# Charging.net
KiCad netlist of a schematic drawn in Altium Designer
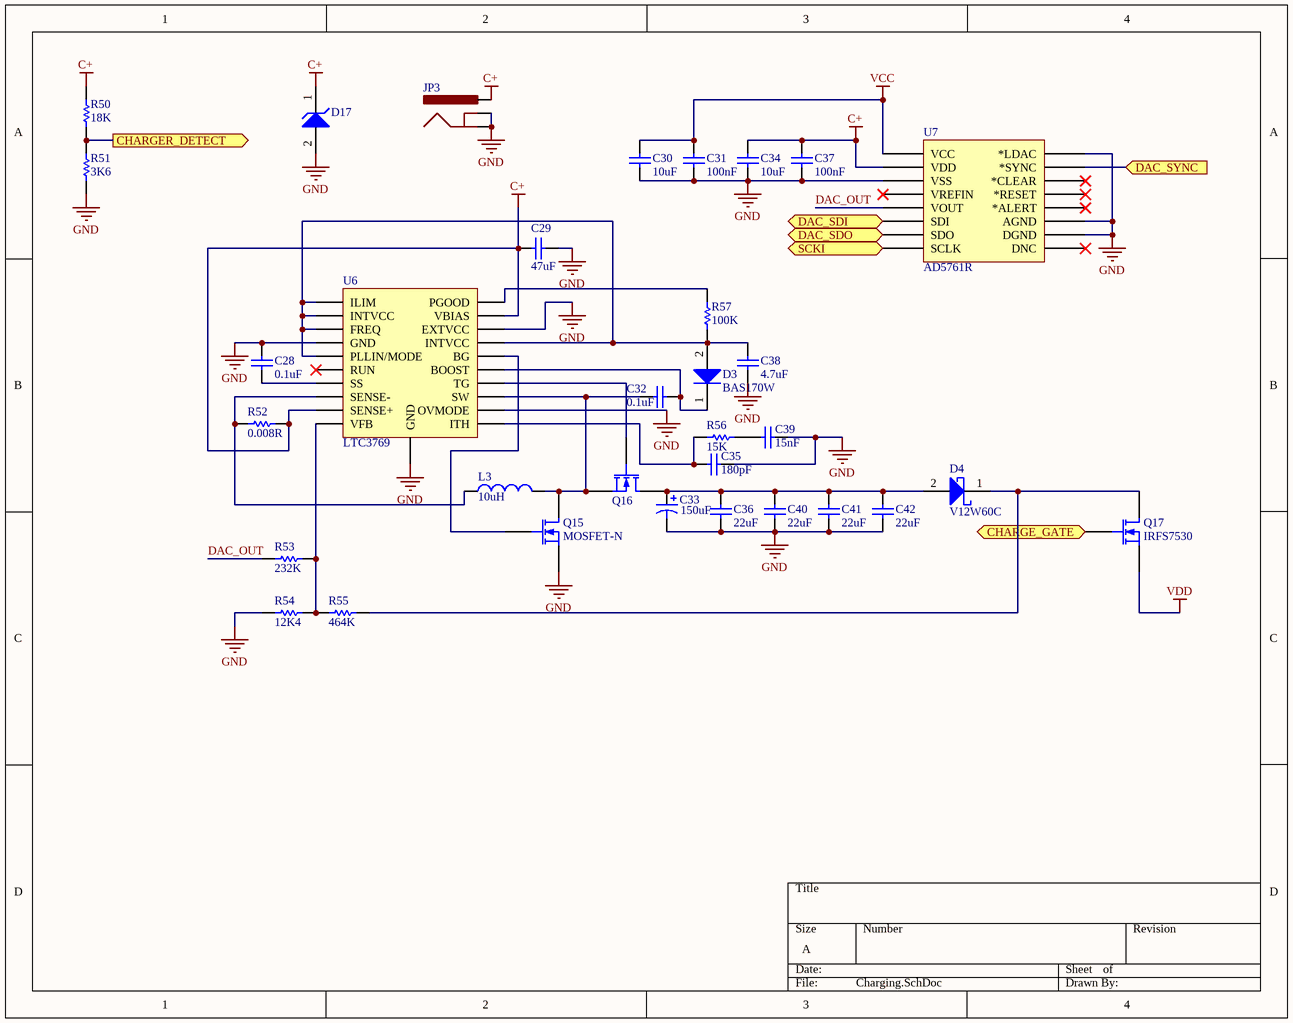
[diagram p0: Charging.SchDoc]

(export (version "E")
  (design (tool "Eeschema 10.0.6"))
  (components
    (comp (ref "C28")
      (value "0.1uF")
      (footprint "CAPC0603(1608)100_M")
      (description "CAP 100nF 6.3V Â±5% 0603 (1608 Metric) Thickness 1mm SMD")
      (fields (field (name "TOLERANCE") "Â±5%"))
      (libsource (lib "Altium Content Vault") (part "CAP"))
    )
    (comp (ref "C29")
      (value "47uF")
      (footprint "CAPC1206(3216)190_M")
      (description "CAP 22uF 25V Â±20% 1206 (3216 Metric) Thickness 1.9mm SMD")
      (fields (field (name "TOLERANCE") "Â±20%"))
      (libsource (lib "Altium Content Vault") (part "CMP-1037-04995-1"))
    )
    (comp (ref "C30")
      (value "10uF")
      (footprint "CAPC0805(2012)145_N")
      (description "CAP 10uF 25V Â±10% 0805 (2012 Metric) Thickness 1.45mm SMD")
      (fields (field (name "TOLERANCE") "Â±10%"))
      (libsource (lib "Altium Content Vault") (part "CAP"))
    )
    (comp (ref "C31")
      (value "100nF")
      (footprint "CAPC0603(1608)100_N")
      (description "CAP 100nF 25V Â±5% 0603 (1608 Metric) Thickness 1mm SMD")
      (fields (field (name "TOLERANCE") "Â±5%"))
      (libsource (lib "Altium Content Vault") (part "CAP"))
    )
    (comp (ref "C32")
      (value "0.1uF")
      (footprint "CAPC0603(1608)100_M")
      (description "CAP 100nF 6.3V Â±5% 0603 (1608 Metric) Thickness 1mm SMD")
      (fields (field (name "TOLERANCE") "Â±5%"))
      (libsource (lib "Altium Content Vault") (part "CAP"))
    )
    (comp (ref "C33")
      (value "150uF")
      (footprint "CAP 180uF 50V")
      (description "Polarized Capacitor (Axial)")
      (fields (field (name "PUBLISHER") "Altium Limited"))
      (libsource (lib "Components") (part "CAP 180uF 50V"))
    )
    (comp (ref "C34")
      (value "10uF")
      (footprint "CAPC0805(2012)145_N")
      (description "CAP 10uF 25V Â±10% 0805 (2012 Metric) Thickness 1.45mm SMD")
      (fields (field (name "TOLERANCE") "Â±10%"))
      (libsource (lib "Altium Content Vault") (part "CAP"))
    )
    (comp (ref "C35")
      (value "180pF")
      (footprint "CAPC0603(1608)100_M")
      (description "CAP 180pF 6.3V Â±5% 0603 (1608 Metric) Thickness 1mm SMD")
      (fields (field (name "TOLERANCE") "Â±5%"))
      (libsource (lib "Altium Content Vault") (part "CAP"))
    )
    (comp (ref "C36")
      (value "22uF")
      (footprint "CAPC2220(5750)230_N")
      (description "CAP 22uF 50V -20% to +80% 2220 (5750 Metric) Thickness 2.2mm SMD")
      (fields (field (name "TOLERANCE") "-20% to +80%"))
      (libsource (lib "Altium Content Vault") (part "CAP"))
    )
    (comp (ref "C37")
      (value "100nF")
      (footprint "CAPC0603(1608)100_N")
      (description "CAP 100nF 25V Â±5% 0603 (1608 Metric) Thickness 1mm SMD")
      (fields (field (name "TOLERANCE") "Â±5%"))
      (libsource (lib "Altium Content Vault") (part "CAP"))
    )
    (comp (ref "C38")
      (value "4.7uF")
      (footprint "CAPC0603(1608)55_M")
      (description "CAP 4.7uF 6.3V Â±10% 0603 (1608 Metric) Thickness 0.55mm SMD")
      (fields (field (name "TOLERANCE") "Â±10%"))
      (libsource (lib "Altium Content Vault") (part "CAP"))
    )
    (comp (ref "C39")
      (value "15nF")
      (footprint "CAPC0603(1608)100_L")
      (description "CAP 15nF 6.3V Â±5% 0603 (1608 Metric) Thickness 1mm SMD")
      (fields (field (name "TOLERANCE") "Â±5%"))
      (libsource (lib "Altium Content Vault") (part "CAP"))
    )
    (comp (ref "C40")
      (value "22uF")
      (footprint "CAPC2220(5750)230_N")
      (description "CAP 22uF 50V -20% to +80% 2220 (5750 Metric) Thickness 2.2mm SMD")
      (fields (field (name "TOLERANCE") "-20% to +80%"))
      (libsource (lib "Altium Content Vault") (part "CAP"))
    )
    (comp (ref "C41")
      (value "22uF")
      (footprint "CAPC2220(5750)230_N")
      (description "CAP 22uF 50V -20% to +80% 2220 (5750 Metric) Thickness 2.2mm SMD")
      (fields (field (name "TOLERANCE") "-20% to +80%"))
      (libsource (lib "Altium Content Vault") (part "CAP"))
    )
    (comp (ref "C42")
      (value "22uF")
      (footprint "CAPC2220(5750)230_N")
      (description "CAP 22uF 50V -20% to +80% 2220 (5750 Metric) Thickness 2.2mm SMD")
      (fields (field (name "TOLERANCE") "-20% to +80%"))
      (libsource (lib "Altium Content Vault") (part "CAP"))
    )
    (comp (ref "D3")
      (value "BAS170W")
      (footprint "INF-SOD323_V")
      (description "Silicon Schottky Diode, -55 to 125 degC, SOD323, Reel, Green")
      (fields (field (name "MANUFACTURER") "Infineon"))
      (libsource (lib "Altium Content Vault") (part "INF-D_K1A2-2"))
    )
    (comp (ref "D4")
      (value "V12W60C")
      (footprint "DPAK229P1003X238-3N")
      (libsource (lib "Components") (part "V12W60C"))
    )
    (comp (ref "D17")
      (value "~")
      (footprint "ONSC-SOD-123-2-425-04_V")
      (description "Zener Voltage Regulator, 500 mW, 2-Pin SOD-123, Pb-Free, Tape and Reel")
      (fields (field (name "PARTNUMBER") "MMSZ24T1G") (field (name "MANUFACTURER") "On Semiconductor"))
      (libsource (lib "Altium Inc") (part "ONSC-K1A2-2"))
    )
    (comp (ref "JP3")
      (value "~")
      (footprint "POWER_JACK_SMD_OVERPASTE_REDBOARD_0603")
      (libsource (lib "SparkFun-Connectors") (part "POWER_JACK1"))
    )
    (comp (ref "L3")
      (value "10uH")
      (footprint "IHLP-6767GZ")
      (description "Inductor")
      (fields (field (name "PUBLISHER") "Altium Limited"))
      (libsource (lib "Components") (part "IHLP6767"))
    )
    (comp (ref "Q15")
      (value "MOSFET-N")
      (footprint "SOIC127P600X175-8N")
      (description "N-Channel MOSFET")
      (fields (field (name "PUBLISHER") "Altium Limited"))
      (libsource (lib "Components") (part "MOSFET-N"))
    )
    (comp (ref "Q16")
      (value "~")
      (footprint "SOIC127P600X175-8N")
      (description "N-Channel MOSFET")
      (fields (field (name "PUBLISHER") "Altium Limited"))
      (libsource (lib "Components") (part "MOSFET-N"))
    )
    (comp (ref "Q17")
      (value "IRFS7530")
      (footprint "DPAK127P1525X483-7N")
      (description "N-Channel MOSFET")
      (fields (field (name "PUBLISHER") "Altium Limited"))
      (libsource (lib "Components") (part "IRFS7530"))
    )
    (comp (ref "R50")
      (value "18K")
      (footprint "RESC0603(1608)_M")
      (description "18K 0.1W 1% 0603 (1608 Metric)  SMD")
      (fields (field (name "POWER") "0.1 W") (field (name "TOLERANCE") "1 %"))
      (libsource (lib "Altium Content Vault") (part "RES"))
    )
    (comp (ref "R51")
      (value "3K6")
      (footprint "RESC0603(1608)_L")
      (description "3K6 0.1W 1% 0603 (1608 Metric)  SMD")
      (fields (field (name "TOLERANCE") "1 %") (field (name "POWER") "0.1 W"))
      (libsource (lib "Altium Content Vault") (part "RES"))
    )
    (comp (ref "R52")
      (value "0.008R")
      (footprint "RESC2010(5025)_L")
      (description "1R 0.75W 5% 2010 (5025 Metric)  SMD")
      (fields (field (name "TOLERANCE") "5 %") (field (name "POWER") "0.75 W"))
      (libsource (lib "Altium Content Vault") (part "CMP-1017-00002-1"))
    )
    (comp (ref "R53")
      (value "232K")
      (footprint "RESC0603(1608)_N")
      (description "232K 0.1W 1% 0603 (1608 Metric)  SMD")
      (fields (field (name "TOLERANCE") "1 %") (field (name "POWER") "0.1 W"))
      (libsource (lib "Altium Content Vault") (part "RES"))
    )
    (comp (ref "R54")
      (value "12K4")
      (footprint "RESC0603(1608)_M")
      (description "12K4 0.1W 1% 0603 (1608 Metric)  SMD")
      (fields (field (name "POWER") "0.1 W") (field (name "TOLERANCE") "1 %"))
      (libsource (lib "Altium Content Vault") (part "RES"))
    )
    (comp (ref "R55")
      (value "464K")
      (footprint "RESC0603(1608)_M")
      (description "464K 0.1W 1% 0603 (1608 Metric)  SMD")
      (fields (field (name "TOLERANCE") "1 %") (field (name "POWER") "0.1 W"))
      (libsource (lib "Altium Content Vault") (part "RES"))
    )
    (comp (ref "R56")
      (value "15K")
      (footprint "RESC0603(1608)_M")
      (description "15K 0.1W 5% 0603 (1608 Metric)  SMD")
      (fields (field (name "POWER") "0.1 W") (field (name "TOLERANCE") "5 %"))
      (libsource (lib "Altium Content Vault") (part "RES"))
    )
    (comp (ref "R57")
      (value "100K")
      (footprint "RESC0603(1608)_N")
      (description "100K 0.1W 5% 0603 (1608 Metric)  SMD")
      (fields (field (name "TOLERANCE") "5 %") (field (name "POWER") "0.1 W"))
      (libsource (lib "Altium Content Vault") (part "RES"))
    )
    (comp (ref "U6")
      (value "LTC3769")
      (footprint "TSOP65P640X120_HS-21N")
      (libsource (lib "Components") (part "LTC3769"))
    )
    (comp (ref "U7")
      (value "AD5761R")
      (footprint "RU_16")
      (description "Imported")
      (libsource (lib "Components") (part "AD5761BRUZ"))
    )
  )
  (nets
    (net (code "1") (name "/CHARGER_DETECT") (class "Default")
      (node (ref "R50") (pin "1") (pinfunction "1_1") (pintype "passive"))
      (node (ref "R51") (pin "2") (pinfunction "2_2") (pintype "passive"))
    )
    (net (code "2") (name "/CHARGE_GATE") (class "Default")
      (node (ref "Q17") (pin "2") (pinfunction "G_2") (pintype "passive"))
    )
    (net (code "3") (name "/DAC_OUT") (class "Default")
      (node (ref "R53") (pin "1") (pinfunction "1_1") (pintype "passive"))
      (node (ref "U7") (pin "7") (pinfunction "VOUT_7") (pintype "passive"))
    )
    (net (code "4") (name "/DAC_SDI") (class "Default")
      (node (ref "U7") (pin "12") (pinfunction "SDI_12") (pintype "passive"))
    )
    (net (code "5") (name "/DAC_SDO") (class "Default")
      (node (ref "U7") (pin "10") (pinfunction "SDO_10") (pintype "passive"))
    )
    (net (code "6") (name "/DAC_SYNC") (class "Default")
      (node (ref "U7") (pin "13") (pinfunction "*SYNC_13") (pintype "passive"))
    )
    (net (code "7") (name "/SCKI") (class "Default")
      (node (ref "U7") (pin "14") (pinfunction "SCLK_14") (pintype "passive"))
    )
    (net (code "8") (name "C+") (class "Default")
      (node (ref "C29") (pin "1") (pinfunction "1_1") (pintype "passive"))
      (node (ref "C34") (pin "2") (pinfunction "2_2") (pintype "passive"))
      (node (ref "C37") (pin "2") (pinfunction "2_2") (pintype "passive"))
      (node (ref "D17") (pin "1") (pinfunction "K_1") (pintype "passive"))
      (node (ref "JP3") (pin "VIN0") (pinfunction "PWR_VIN0") (pintype "passive"))
      (node (ref "R50") (pin "2") (pinfunction "2_2") (pintype "passive"))
      (node (ref "R52") (pin "2") (pinfunction "2_2") (pintype "passive"))
      (node (ref "U6") (pin "19") (pinfunction "VBIAS_19") (pintype "passive"))
      (node (ref "U6") (pin "9") (pinfunction "SENSE+_9") (pintype "passive"))
      (node (ref "U7") (pin "8") (pinfunction "VDD_8") (pintype "passive"))
    )
    (net (code "9") (name "GND") (class "Default")
      (node (ref "C28") (pin "2") (pinfunction "2_2") (pintype "passive"))
      (node (ref "C29") (pin "2") (pinfunction "2_2") (pintype "passive"))
      (node (ref "C30") (pin "1") (pinfunction "1_1") (pintype "passive"))
      (node (ref "C31") (pin "1") (pinfunction "1_1") (pintype "passive"))
      (node (ref "C33") (pin "2") (pinfunction "2_2") (pintype "passive"))
      (node (ref "C34") (pin "1") (pinfunction "1_1") (pintype "passive"))
      (node (ref "C35") (pin "2") (pinfunction "2_2") (pintype "passive"))
      (node (ref "C36") (pin "1") (pinfunction "1_1") (pintype "passive"))
      (node (ref "C37") (pin "1") (pinfunction "1_1") (pintype "passive"))
      (node (ref "C38") (pin "1") (pinfunction "1_1") (pintype "passive"))
      (node (ref "C39") (pin "2") (pinfunction "2_2") (pintype "passive"))
      (node (ref "C40") (pin "1") (pinfunction "1_1") (pintype "passive"))
      (node (ref "C41") (pin "1") (pinfunction "1_1") (pintype "passive"))
      (node (ref "C42") (pin "1") (pinfunction "1_1") (pintype "passive"))
      (node (ref "D17") (pin "2") (pinfunction "A_2") (pintype "passive"))
      (node (ref "JP3") (pin "GND") (pinfunction "GNDBREAK_GND") (pintype "passive"))
      (node (ref "JP3") (pin "P$4") (pinfunction "GND_P$4") (pintype "passive"))
      (node (ref "Q15") (pin "3") (pinfunction "S_3") (pintype "passive"))
      (node (ref "R51") (pin "1") (pinfunction "1_1") (pintype "passive"))
      (node (ref "R54") (pin "1") (pinfunction "1_1") (pintype "passive"))
      (node (ref "U6") (pin "12") (pinfunction "OVMODE_12") (pintype "passive"))
      (node (ref "U6") (pin "18") (pinfunction "EXTVCC_18") (pintype "passive"))
      (node (ref "U6") (pin "21") (pinfunction "GND_21") (pintype "passive"))
      (node (ref "U6") (pin "4") (pinfunction "GND_4") (pintype "passive"))
      (node (ref "U7") (pin "11") (pinfunction "*LDAC_11") (pintype "passive"))
      (node (ref "U7") (pin "16") (pinfunction "DGND_16") (pintype "passive"))
      (node (ref "U7") (pin "5") (pinfunction "AGND_5") (pintype "passive"))
      (node (ref "U7") (pin "6") (pinfunction "VSS_6") (pintype "passive"))
    )
    (net (code "10") (name "Net-(C39-Pad1)") (class "Default")
      (node (ref "C39") (pin "1") (pinfunction "1_1") (pintype "passive"))
      (node (ref "R56") (pin "2") (pinfunction "2_2") (pintype "passive"))
    )
    (net (code "11") (name "Net-(D3-A)") (class "Default")
      (node (ref "C38") (pin "2") (pinfunction "2_2") (pintype "passive"))
      (node (ref "D3") (pin "2") (pinfunction "A_2") (pintype "passive"))
      (node (ref "R57") (pin "1") (pinfunction "1_1") (pintype "passive"))
      (node (ref "U6") (pin "1") (pinfunction "ILIM_1") (pintype "passive"))
      (node (ref "U6") (pin "17") (pinfunction "INTVCC_17") (pintype "passive"))
      (node (ref "U6") (pin "2") (pinfunction "INTVCC_2") (pintype "passive"))
      (node (ref "U6") (pin "3") (pinfunction "FREQ_3") (pintype "passive"))
      (node (ref "U6") (pin "5") (pinfunction "PLLIN/MODE_5") (pintype "passive"))
    )
    (net (code "12") (name "Net-(D3-K)") (class "Default")
      (node (ref "C32") (pin "2") (pinfunction "2_2") (pintype "passive"))
      (node (ref "D3") (pin "1") (pinfunction "K_1") (pintype "passive"))
      (node (ref "U6") (pin "15") (pinfunction "BOOST_15") (pintype "passive"))
    )
    (net (code "13") (name "Net-(D4-A)") (class "Default")
      (node (ref "C33") (pin "1") (pinfunction "1_1") (pintype "passive"))
      (node (ref "C36") (pin "2") (pinfunction "2_2") (pintype "passive"))
      (node (ref "C40") (pin "2") (pinfunction "2_2") (pintype "passive"))
      (node (ref "C41") (pin "2") (pinfunction "2_2") (pintype "passive"))
      (node (ref "C42") (pin "2") (pinfunction "2_2") (pintype "passive"))
      (node (ref "D4") (pin "2") (pinfunction "A_2") (pintype "passive"))
      (node (ref "Q16") (pin "2") (pinfunction "D_2") (pintype "passive"))
    )
    (net (code "14") (name "Net-(D4-K)") (class "Default")
      (node (ref "D4") (pin "1") (pinfunction "K_1") (pintype "passive"))
      (node (ref "Q17") (pin "1") (pinfunction "D_1") (pintype "passive"))
      (node (ref "R55") (pin "2") (pinfunction "2_2") (pintype "passive"))
    )
    (net (code "15") (name "Net-(Q15-D)") (class "Default")
      (node (ref "C32") (pin "1") (pinfunction "1_1") (pintype "passive"))
      (node (ref "L3") (pin "2") (pinfunction "2_2") (pintype "passive"))
      (node (ref "Q15") (pin "2") (pinfunction "D_2") (pintype "passive"))
      (node (ref "Q16") (pin "3") (pinfunction "S_3") (pintype "passive"))
      (node (ref "U6") (pin "13") (pinfunction "SW_13") (pintype "passive"))
    )
    (net (code "16") (name "Net-(Q15-G)") (class "Default")
      (node (ref "Q15") (pin "1") (pinfunction "G_1") (pintype "passive"))
      (node (ref "U6") (pin "16") (pinfunction "BG_16") (pintype "passive"))
    )
    (net (code "17") (name "Net-(Q16-G)") (class "Default")
      (node (ref "Q16") (pin "1") (pinfunction "G_1") (pintype "passive"))
      (node (ref "U6") (pin "14") (pinfunction "TG_14") (pintype "passive"))
    )
    (net (code "18") (name "Net-(U6-ITH)") (class "Default")
      (node (ref "C35") (pin "1") (pinfunction "1_1") (pintype "passive"))
      (node (ref "R56") (pin "1") (pinfunction "1_1") (pintype "passive"))
      (node (ref "U6") (pin "11") (pinfunction "ITH_11") (pintype "passive"))
    )
    (net (code "19") (name "Net-(U6-PGOOD)") (class "Default")
      (node (ref "R57") (pin "2") (pinfunction "2_2") (pintype "passive"))
      (node (ref "U6") (pin "20") (pinfunction "PGOOD_20") (pintype "passive"))
    )
    (net (code "20") (name "Net-(U6-SENSE-)") (class "Default")
      (node (ref "L3") (pin "1") (pinfunction "1_1") (pintype "passive"))
      (node (ref "R52") (pin "1") (pinfunction "1_1") (pintype "passive"))
      (node (ref "U6") (pin "8") (pinfunction "SENSE-_8") (pintype "passive"))
    )
    (net (code "21") (name "Net-(U6-SS)") (class "Default")
      (node (ref "C28") (pin "1") (pinfunction "1_1") (pintype "passive"))
      (node (ref "U6") (pin "7") (pinfunction "SS_7") (pintype "passive"))
    )
    (net (code "22") (name "Net-(U6-VFB)") (class "Default")
      (node (ref "R53") (pin "2") (pinfunction "2_2") (pintype "passive"))
      (node (ref "R54") (pin "2") (pinfunction "2_2") (pintype "passive"))
      (node (ref "R55") (pin "1") (pinfunction "1_1") (pintype "passive"))
      (node (ref "U6") (pin "10") (pinfunction "VFB_10") (pintype "passive"))
    )
    (net (code "23") (name "VCC") (class "Default")
      (node (ref "C30") (pin "2") (pinfunction "2_2") (pintype "passive"))
      (node (ref "C31") (pin "2") (pinfunction "2_2") (pintype "passive"))
      (node (ref "U7") (pin "15") (pinfunction "VCC_15") (pintype "passive"))
    )
    (net (code "24") (name "VDD") (class "Default")
      (node (ref "Q17") (pin "3") (pinfunction "S_3") (pintype "passive"))
    )
    (net (code "25") (name "unconnected-(U6-RUN-Pad6)") (class "Default")
      (node (ref "U6") (pin "6") (pinfunction "RUN_6") (pintype "passive+no_connect"))
    )
    (net (code "26") (name "unconnected-(U7-*ALERT-Pad1)") (class "Default")
      (node (ref "U7") (pin "1") (pinfunction "*ALERT_1") (pintype "passive+no_connect"))
    )
    (net (code "27") (name "unconnected-(U7-*CLEAR-Pad2)") (class "Default")
      (node (ref "U7") (pin "2") (pinfunction "*CLEAR_2") (pintype "passive+no_connect"))
    )
    (net (code "28") (name "unconnected-(U7-*RESET-Pad3)") (class "Default")
      (node (ref "U7") (pin "3") (pinfunction "*RESET_3") (pintype "passive+no_connect"))
    )
    (net (code "29") (name "unconnected-(U7-DNC-Pad9)") (class "Default")
      (node (ref "U7") (pin "9") (pinfunction "DNC_9") (pintype "passive+no_connect"))
    )
    (net (code "30") (name "unconnected-(U7-VREFIN-Pad4)") (class "Default")
      (node (ref "U7") (pin "4") (pinfunction "VREFIN_4") (pintype "passive+no_connect"))
    )
  )
)
